# DiplomskiRad.net
KiCad netlist of a schematic drawn in Altium Designer
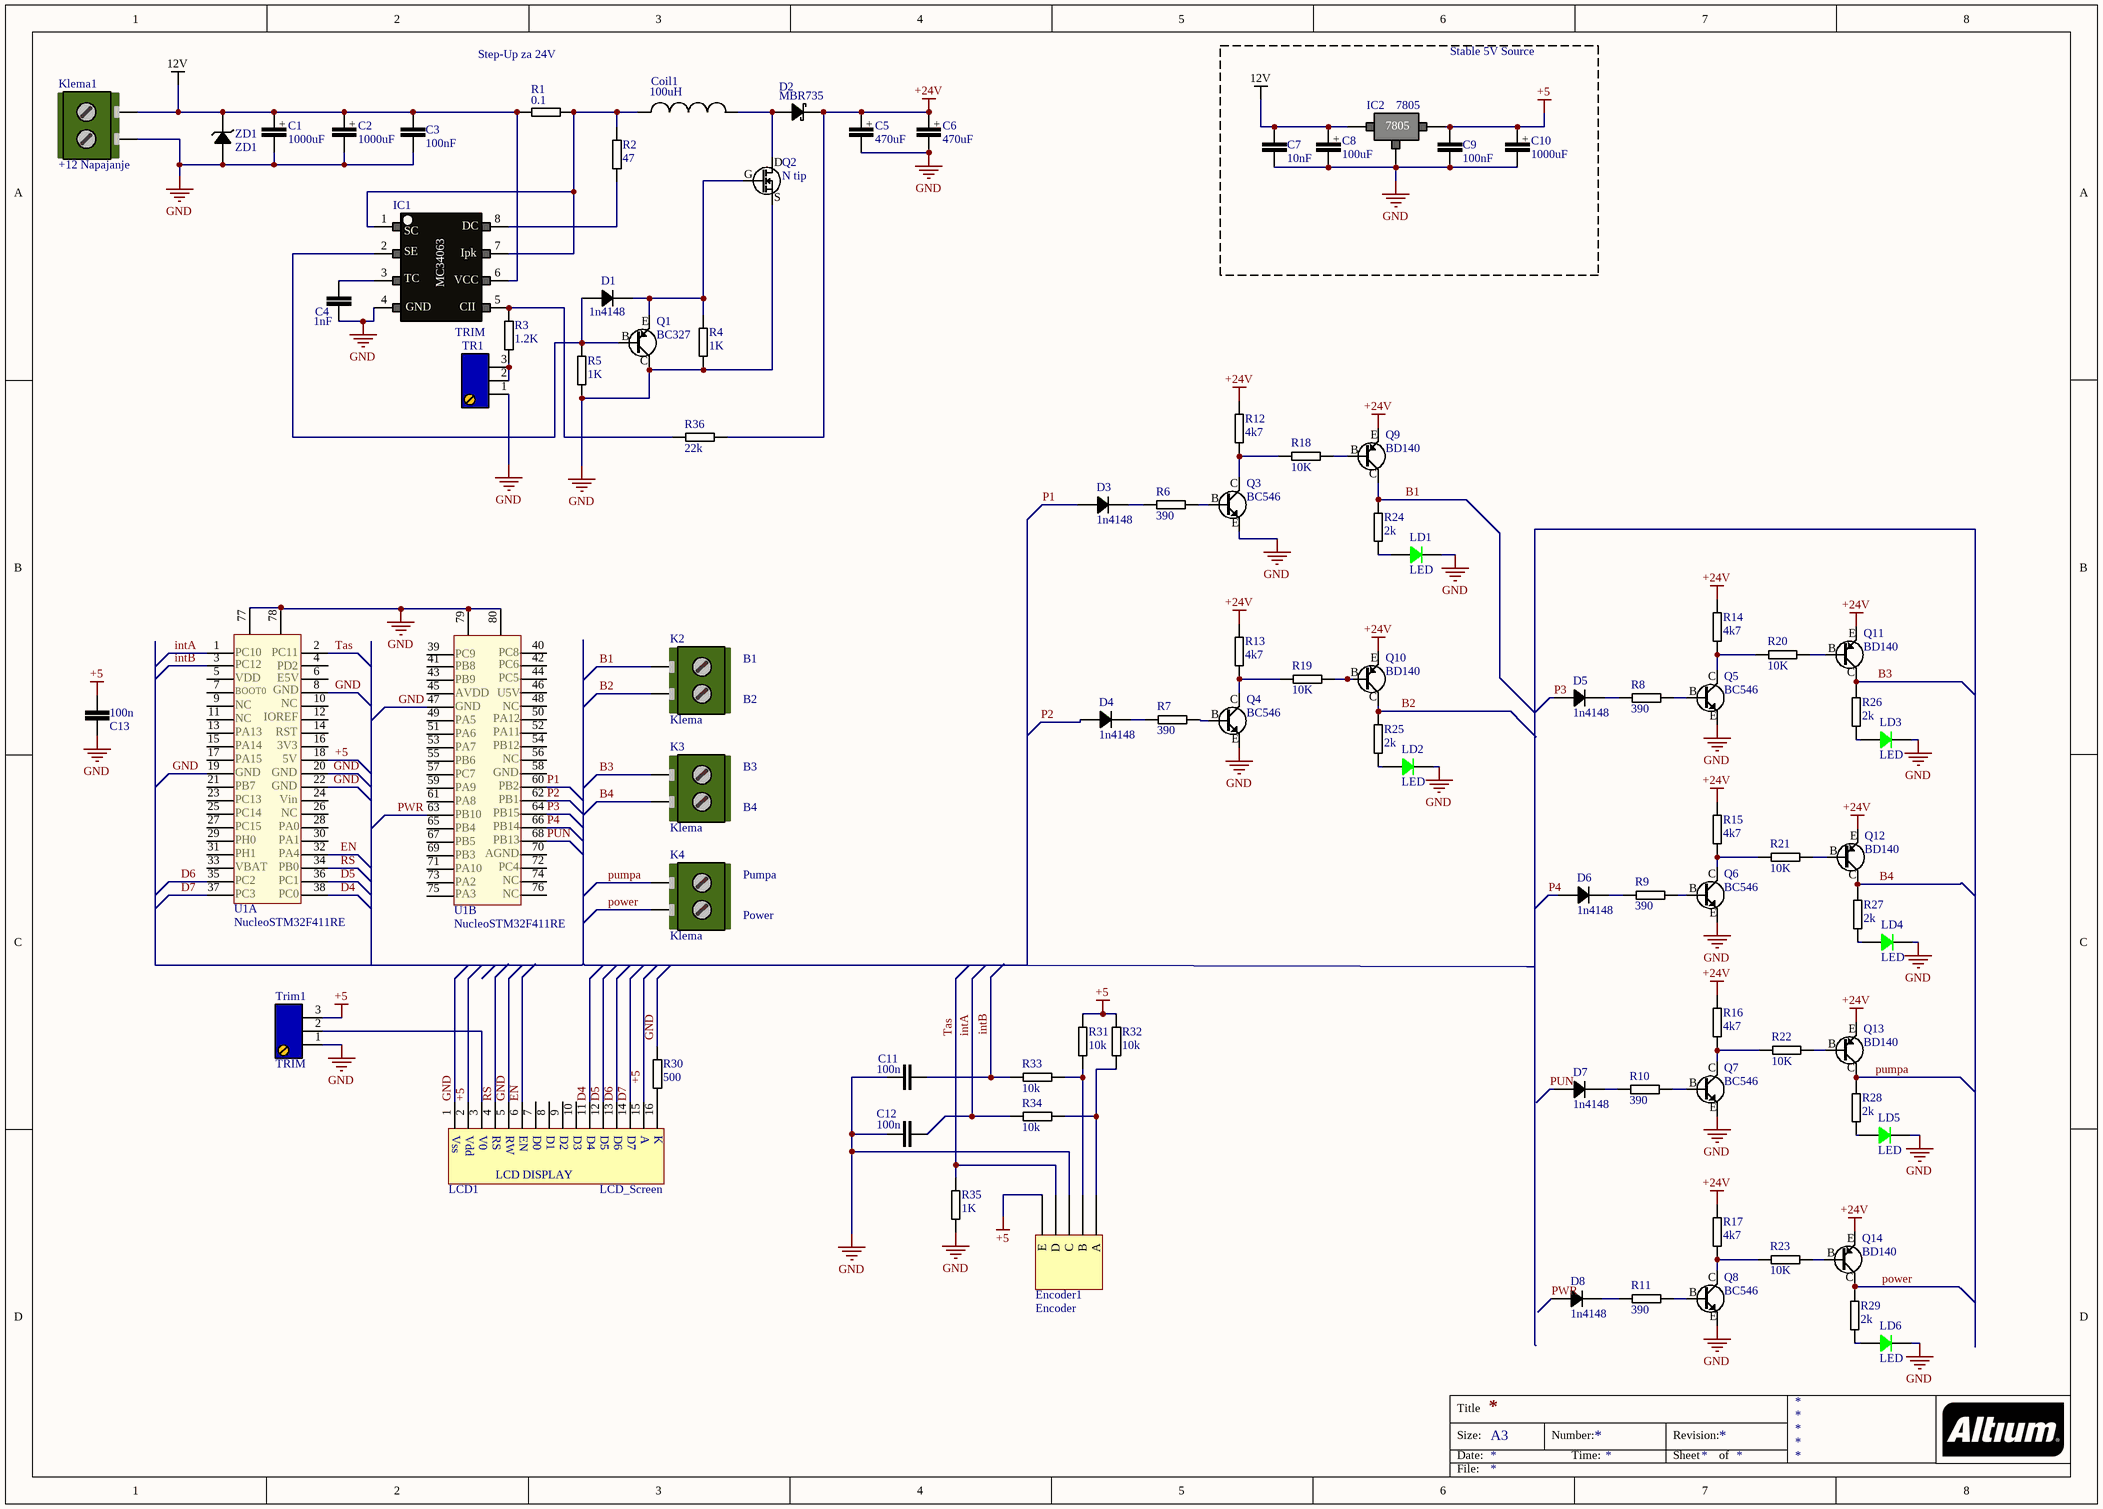
[diagram p0: DiplomskiRad.SchDoc]

(export (version "E")
  (design (tool "Eeschema 10.0.6"))
  (components
    (comp (ref "100n") (value "C13") (footprint "C1(ceramic)") (libsource (lib "KILEX LIB SCH") (part "C1")))
    (comp (ref "C1")
      (value "1000uF")
      (footprint "C2(elektrolit)")
      (libsource (lib "KILEX LIB SCH") (part "C2"))
    )
    (comp (ref "C2")
      (value "1000uF")
      (footprint "C2(elektrolit)")
      (libsource (lib "KILEX LIB SCH") (part "C2"))
    )
    (comp (ref "C3") (value "100nF") (footprint "C1(ceramic)") (libsource (lib "KILEX LIB SCH") (part "C1")))
    (comp (ref "C4") (value "1nF") (footprint "C1(ceramic)") (libsource (lib "KILEX LIB SCH") (part "C1")))
    (comp (ref "C5")
      (value "470uF")
      (footprint "C2(elektrolit)")
      (libsource (lib "KILEX LIB SCH") (part "C2"))
    )
    (comp (ref "C6")
      (value "470uF")
      (footprint "C2(elektrolit)")
      (libsource (lib "KILEX LIB SCH") (part "C2"))
    )
    (comp (ref "C7") (value "10nF") (footprint "C1(ceramic)") (libsource (lib "KILEX LIB SCH") (part "C1")))
    (comp (ref "C8")
      (value "100uF")
      (footprint "C2(elektrolit)")
      (libsource (lib "KILEX LIB SCH") (part "C2"))
    )
    (comp (ref "C9") (value "100nF") (footprint "C1(ceramic)") (libsource (lib "KILEX LIB SCH") (part "C1")))
    (comp (ref "C10")
      (value "1000uF")
      (footprint "C2(elektrolit)")
      (libsource (lib "KILEX LIB SCH") (part "C2"))
    )
    (comp (ref "C11") (value "100n") (footprint "C1(ceramic)") (libsource (lib "KILEX LIB SCH") (part "C1")))
    (comp (ref "C12") (value "100n") (footprint "C1(ceramic)") (libsource (lib "KILEX LIB SCH") (part "C1")))
    (comp (ref "Coil1")
      (value "100uH")
      (footprint "Coil_14x8")
      (libsource (lib "KILEX LIB SCH") (part "Coil"))
    )
    (comp (ref "D1")
      (value "1n4148")
      (footprint "D1(300milsa)")
      (libsource (lib "KILEX LIB SCH") (part "D1"))
    )
    (comp (ref "D2")
      (value "MBR735")
      (footprint "D2(TO220)")
      (libsource (lib "KILEX LIB SCH") (part "Sotki Diode"))
    )
    (comp (ref "D3")
      (value "1n4148")
      (footprint "D1(300milsa)")
      (libsource (lib "KILEX LIB SCH") (part "D1"))
    )
    (comp (ref "D4")
      (value "1n4148")
      (footprint "D1(300milsa)")
      (libsource (lib "KILEX LIB SCH") (part "D1"))
    )
    (comp (ref "D5")
      (value "1n4148")
      (footprint "D1(300milsa)")
      (libsource (lib "KILEX LIB SCH") (part "D1"))
    )
    (comp (ref "D6")
      (value "1n4148")
      (footprint "D1(300milsa)")
      (libsource (lib "KILEX LIB SCH") (part "D1"))
    )
    (comp (ref "D7")
      (value "1n4148")
      (footprint "D1(300milsa)")
      (libsource (lib "KILEX LIB SCH") (part "D1"))
    )
    (comp (ref "D8")
      (value "1n4148")
      (footprint "D1(300milsa)")
      (libsource (lib "KILEX LIB SCH") (part "D1"))
    )
    (comp (ref "Encoder1")
      (value "Encoder")
      (footprint "Encoder")
      (libsource (lib "KILEX LIB SCH") (part "Encoder"))
    )
    (comp (ref "IC1") (value "~") (footprint "DIP8") (libsource (lib "KILEX LIB SCH") (part "MC34063")))
    (comp (ref "IC2") (value "7805") (footprint "TO220") (libsource (lib "KILEX LIB SCH") (part "7805")))
    (comp (ref "K2") (value "Klema") (footprint "Klema") (libsource (lib "") (part "Klema_1")))
    (comp (ref "K3") (value "Klema") (footprint "Klema") (libsource (lib "") (part "Klema_1")))
    (comp (ref "K4") (value "Klema") (footprint "Klema") (libsource (lib "") (part "Klema_1")))
    (comp (ref "Klema1")
      (value "+12 Napajanje")
      (footprint "Klema")
      (libsource (lib "KILEX LIB SCH") (part "Klema"))
    )
    (comp (ref "LCD1")
      (value "LCD_Screen")
      (footprint "LCD_Screen")
      (libsource (lib "KILEX LIB SCH") (part "LCD_Screen"))
    )
    (comp (ref "LD1") (value "LED") (footprint "LED(3mm)") (libsource (lib "KILEX LIB SCH") (part "LED")))
    (comp (ref "LD2") (value "LED") (footprint "LED(3mm)") (libsource (lib "KILEX LIB SCH") (part "LED")))
    (comp (ref "LD3") (value "LED") (footprint "LED(3mm)") (libsource (lib "KILEX LIB SCH") (part "LED")))
    (comp (ref "LD4") (value "LED") (footprint "LED(3mm)") (libsource (lib "KILEX LIB SCH") (part "LED")))
    (comp (ref "LD5") (value "LED") (footprint "LED(3mm)") (libsource (lib "KILEX LIB SCH") (part "LED")))
    (comp (ref "LD6") (value "LED") (footprint "LED(3mm)") (libsource (lib "KILEX LIB SCH") (part "LED")))
    (comp (ref "Q1")
      (value "BC327")
      (footprint "TO-92")
      (libsource (lib "KILEX LIB SCH") (part "Transistor PNP"))
    )
    (comp (ref "Q2")
      (value "N tip")
      (footprint "N-Channel MOSFET")
      (libsource (lib "KILEX LIB SCH") (part "N-Channel MOSFET"))
    )
    (comp (ref "Q3")
      (value "BC546")
      (footprint "TO-92")
      (libsource (lib "KILEX LIB SCH") (part "Transistor NPN"))
    )
    (comp (ref "Q4")
      (value "BC546")
      (footprint "TO-92")
      (libsource (lib "KILEX LIB SCH") (part "Transistor NPN"))
    )
    (comp (ref "Q5")
      (value "BC546")
      (footprint "TO-92")
      (libsource (lib "KILEX LIB SCH") (part "Transistor NPN"))
    )
    (comp (ref "Q6")
      (value "BC546")
      (footprint "TO-92")
      (libsource (lib "KILEX LIB SCH") (part "Transistor NPN"))
    )
    (comp (ref "Q7")
      (value "BC546")
      (footprint "TO-92")
      (libsource (lib "KILEX LIB SCH") (part "Transistor NPN"))
    )
    (comp (ref "Q8")
      (value "BC546")
      (footprint "TO-92")
      (libsource (lib "KILEX LIB SCH") (part "Transistor NPN"))
    )
    (comp (ref "Q9") (value "BD140") (footprint "TO126") (libsource (lib "KILEX LIB SCH") (part "BD140")))
    (comp (ref "Q10") (value "BD140") (footprint "TO126") (libsource (lib "KILEX LIB SCH") (part "BD140")))
    (comp (ref "Q11") (value "BD140") (footprint "TO126") (libsource (lib "KILEX LIB SCH") (part "BD140")))
    (comp (ref "Q12") (value "BD140") (footprint "TO126") (libsource (lib "KILEX LIB SCH") (part "BD140")))
    (comp (ref "Q13") (value "BD140") (footprint "TO126") (libsource (lib "KILEX LIB SCH") (part "BD140")))
    (comp (ref "Q14") (value "BD140") (footprint "TO126") (libsource (lib "KILEX LIB SCH") (part "BD140")))
    (comp (ref "R1") (value "0.1") (footprint "R1(2W)") (libsource (lib "KILEX LIB SCH") (part "R1")))
    (comp (ref "R2") (value "47") (footprint "R1(300milsa)") (libsource (lib "KILEX LIB SCH") (part "R1")))
    (comp (ref "R3") (value "1.2K") (footprint "R1(300milsa)") (libsource (lib "KILEX LIB SCH") (part "R1")))
    (comp (ref "R4") (value "1K") (footprint "R1(300milsa)") (libsource (lib "KILEX LIB SCH") (part "R1")))
    (comp (ref "R5") (value "1K") (footprint "R1(300milsa)") (libsource (lib "KILEX LIB SCH") (part "R1")))
    (comp (ref "R6") (value "390") (footprint "R1(300milsa)") (libsource (lib "KILEX LIB SCH") (part "R1")))
    (comp (ref "R7") (value "390") (footprint "R1(300milsa)") (libsource (lib "KILEX LIB SCH") (part "R1")))
    (comp (ref "R8") (value "390") (footprint "R1(300milsa)") (libsource (lib "KILEX LIB SCH") (part "R1")))
    (comp (ref "R9") (value "390") (footprint "R1(300milsa)") (libsource (lib "KILEX LIB SCH") (part "R1")))
    (comp (ref "R10") (value "390") (footprint "R1(300milsa)") (libsource (lib "KILEX LIB SCH") (part "R1")))
    (comp (ref "R11") (value "390") (footprint "R1(300milsa)") (libsource (lib "KILEX LIB SCH") (part "R1")))
    (comp (ref "R12") (value "4k7") (footprint "R1(300milsa)") (libsource (lib "KILEX LIB SCH") (part "R1")))
    (comp (ref "R13") (value "4k7") (footprint "R1(300milsa)") (libsource (lib "KILEX LIB SCH") (part "R1")))
    (comp (ref "R14") (value "4k7") (footprint "R1(300milsa)") (libsource (lib "KILEX LIB SCH") (part "R1")))
    (comp (ref "R15") (value "4k7") (footprint "R1(300milsa)") (libsource (lib "KILEX LIB SCH") (part "R1")))
    (comp (ref "R16") (value "4k7") (footprint "R1(300milsa)") (libsource (lib "KILEX LIB SCH") (part "R1")))
    (comp (ref "R17") (value "4k7") (footprint "R1(300milsa)") (libsource (lib "KILEX LIB SCH") (part "R1")))
    (comp (ref "R18") (value "10K") (footprint "R1(300milsa)") (libsource (lib "KILEX LIB SCH") (part "R1")))
    (comp (ref "R19") (value "10K") (footprint "R1(300milsa)") (libsource (lib "KILEX LIB SCH") (part "R1")))
    (comp (ref "R20") (value "10K") (footprint "R1(300milsa)") (libsource (lib "KILEX LIB SCH") (part "R1")))
    (comp (ref "R21") (value "10K") (footprint "R1(300milsa)") (libsource (lib "KILEX LIB SCH") (part "R1")))
    (comp (ref "R22") (value "10K") (footprint "R1(300milsa)") (libsource (lib "KILEX LIB SCH") (part "R1")))
    (comp (ref "R23") (value "10K") (footprint "R1(300milsa)") (libsource (lib "KILEX LIB SCH") (part "R1")))
    (comp (ref "R24") (value "2k") (footprint "R1(300milsa)") (libsource (lib "KILEX LIB SCH") (part "R1")))
    (comp (ref "R25") (value "2k") (footprint "R1(300milsa)") (libsource (lib "KILEX LIB SCH") (part "R1")))
    (comp (ref "R26") (value "2k") (footprint "R1(300milsa)") (libsource (lib "KILEX LIB SCH") (part "R1")))
    (comp (ref "R27") (value "2k") (footprint "R1(300milsa)") (libsource (lib "KILEX LIB SCH") (part "R1")))
    (comp (ref "R28") (value "2k") (footprint "R1(300milsa)") (libsource (lib "KILEX LIB SCH") (part "R1")))
    (comp (ref "R29") (value "2k") (footprint "R1(300milsa)") (libsource (lib "KILEX LIB SCH") (part "R1")))
    (comp (ref "R30") (value "500") (footprint "R1(300milsa)") (libsource (lib "KILEX LIB SCH") (part "R1")))
    (comp (ref "R31") (value "10k") (footprint "R1(300milsa)") (libsource (lib "KILEX LIB SCH") (part "R1")))
    (comp (ref "R32") (value "10k") (footprint "R1(300milsa)") (libsource (lib "KILEX LIB SCH") (part "R1")))
    (comp (ref "R33") (value "10k") (footprint "R1(300milsa)") (libsource (lib "KILEX LIB SCH") (part "R1")))
    (comp (ref "R34") (value "10k") (footprint "R1(300milsa)") (libsource (lib "KILEX LIB SCH") (part "R1")))
    (comp (ref "R35") (value "1K") (footprint "R1(300milsa)") (libsource (lib "KILEX LIB SCH") (part "R1")))
    (comp (ref "R36") (value "22k") (footprint "R1(300milsa)") (libsource (lib "KILEX LIB SCH") (part "R1")))
    (comp (ref "TR1") (value "TRIM") (footprint "TRIM") (libsource (lib "KILEX LIB SCH") (part "TRIM")))
    (comp (ref "Trim1") (value "TRIM") (footprint "TRIM") (libsource (lib "KILEX LIB SCH") (part "TRIM")))
    (comp (ref "U1")
      (value "NucleoSTM32F411RE")
      (footprint "Nucleo411")
      (libsource (lib "KILEX LIB SCH") (part "NucleoSTM32F411RE"))
    )
    (comp (ref "ZD1") (value "ZD1") (footprint "D1(300milsa)") (libsource (lib "KILEX LIB SCH") (part "ZD1")))
  )
  (nets
    (net (code "1") (name "+5") (class "Default")
      (node (ref "100n") (pin "2") (pinfunction "2_2") (pintype "passive"))
      (node (ref "C10") (pin "1") (pinfunction "1_1") (pintype "passive"))
      (node (ref "C9") (pin "1") (pinfunction "1_1") (pintype "passive"))
      (node (ref "Encoder1") (pin "5") (pinfunction "E_5") (pintype "passive"))
      (node (ref "IC2") (pin "3") (pinfunction "3_3") (pintype "passive"))
      (node (ref "LCD1") (pin "15") (pinfunction "15_15") (pintype "passive"))
      (node (ref "LCD1") (pin "2") (pinfunction "2_2") (pintype "passive"))
      (node (ref "R31") (pin "2") (pinfunction "2_2") (pintype "passive"))
      (node (ref "R32") (pin "2") (pinfunction "2_2") (pintype "passive"))
      (node (ref "Trim1") (pin "3") (pinfunction "3_3") (pintype "passive"))
      (node (ref "U1") (pin "18") (pinfunction "10_18") (pintype "passive"))
    )
    (net (code "2") (name "+24V") (class "Default")
      (node (ref "C5") (pin "1") (pinfunction "1_1") (pintype "passive"))
      (node (ref "C6") (pin "1") (pinfunction "1_1") (pintype "passive"))
      (node (ref "D2") (pin "2") (pinfunction "2_2") (pintype "passive"))
      (node (ref "Q10") (pin "1") (pinfunction "1_1") (pintype "passive"))
      (node (ref "Q11") (pin "1") (pinfunction "1_1") (pintype "passive"))
      (node (ref "Q12") (pin "1") (pinfunction "1_1") (pintype "passive"))
      (node (ref "Q13") (pin "1") (pinfunction "1_1") (pintype "passive"))
      (node (ref "Q14") (pin "1") (pinfunction "1_1") (pintype "passive"))
      (node (ref "Q9") (pin "1") (pinfunction "1_1") (pintype "passive"))
      (node (ref "R12") (pin "2") (pinfunction "2_2") (pintype "passive"))
      (node (ref "R13") (pin "2") (pinfunction "2_2") (pintype "passive"))
      (node (ref "R14") (pin "2") (pinfunction "2_2") (pintype "passive"))
      (node (ref "R15") (pin "2") (pinfunction "2_2") (pintype "passive"))
      (node (ref "R16") (pin "2") (pinfunction "2_2") (pintype "passive"))
      (node (ref "R17") (pin "2") (pinfunction "2_2") (pintype "passive"))
      (node (ref "R36") (pin "2") (pinfunction "2_2") (pintype "passive"))
    )
    (net (code "3") (name "/B1") (class "Default")
      (node (ref "K2") (pin "1") (pinfunction "1_1") (pintype "passive"))
      (node (ref "Q9") (pin "2") (pinfunction "2_2") (pintype "passive"))
      (node (ref "R24") (pin "1") (pinfunction "1_1") (pintype "passive"))
    )
    (net (code "4") (name "/B2") (class "Default")
      (node (ref "K2") (pin "2") (pinfunction "2_2") (pintype "passive"))
      (node (ref "Q10") (pin "2") (pinfunction "2_2") (pintype "passive"))
      (node (ref "R25") (pin "1") (pinfunction "1_1") (pintype "passive"))
    )
    (net (code "5") (name "/B3") (class "Default")
      (node (ref "K3") (pin "1") (pinfunction "1_1") (pintype "passive"))
      (node (ref "Q11") (pin "2") (pinfunction "2_2") (pintype "passive"))
      (node (ref "R26") (pin "1") (pinfunction "1_1") (pintype "passive"))
    )
    (net (code "6") (name "/B4") (class "Default")
      (node (ref "K3") (pin "2") (pinfunction "2_2") (pintype "passive"))
      (node (ref "Q12") (pin "2") (pinfunction "2_2") (pintype "passive"))
      (node (ref "R27") (pin "1") (pinfunction "1_1") (pintype "passive"))
    )
    (net (code "7") (name "/D4") (class "Default")
      (node (ref "LCD1") (pin "11") (pinfunction "11_11") (pintype "passive"))
      (node (ref "U1") (pin "38") (pinfunction "20_38") (pintype "passive"))
    )
    (net (code "8") (name "/D5") (class "Default")
      (node (ref "LCD1") (pin "12") (pinfunction "12_12") (pintype "passive"))
      (node (ref "U1") (pin "36") (pinfunction "19_36") (pintype "passive"))
    )
    (net (code "9") (name "/D6") (class "Default")
      (node (ref "LCD1") (pin "13") (pinfunction "13_13") (pintype "passive"))
      (node (ref "U1") (pin "35") (pinfunction "18_35") (pintype "passive"))
    )
    (net (code "10") (name "/D7") (class "Default")
      (node (ref "LCD1") (pin "14") (pinfunction "14_14") (pintype "passive"))
      (node (ref "U1") (pin "37") (pinfunction "19_37") (pintype "passive"))
    )
    (net (code "11") (name "/EN") (class "Default")
      (node (ref "LCD1") (pin "6") (pinfunction "6_6") (pintype "passive"))
      (node (ref "U1") (pin "32") (pinfunction "17_32") (pintype "passive"))
    )
    (net (code "12") (name "/P1") (class "Default")
      (node (ref "D3") (pin "1") (pinfunction "1_1") (pintype "passive"))
      (node (ref "U1") (pin "60") (pinfunction "50_60") (pintype "passive"))
    )
    (net (code "13") (name "/P2") (class "Default")
      (node (ref "D4") (pin "1") (pinfunction "1_1") (pintype "passive"))
      (node (ref "U1") (pin "62") (pinfunction "51_62") (pintype "passive"))
    )
    (net (code "14") (name "/P3") (class "Default")
      (node (ref "D5") (pin "1") (pinfunction "1_1") (pintype "passive"))
      (node (ref "U1") (pin "64") (pinfunction "52_64") (pintype "passive"))
    )
    (net (code "15") (name "/P4") (class "Default")
      (node (ref "D6") (pin "1") (pinfunction "1_1") (pintype "passive"))
      (node (ref "U1") (pin "66") (pinfunction "53_66") (pintype "passive"))
    )
    (net (code "16") (name "/PUN") (class "Default")
      (node (ref "D7") (pin "1") (pinfunction "1_1") (pintype "passive"))
      (node (ref "U1") (pin "68") (pinfunction "54_68") (pintype "passive"))
    )
    (net (code "17") (name "/PWR") (class "Default")
      (node (ref "D8") (pin "1") (pinfunction "1_1") (pintype "passive"))
      (node (ref "U1") (pin "63") (pinfunction "51_63") (pintype "passive"))
    )
    (net (code "18") (name "/RS") (class "Default")
      (node (ref "LCD1") (pin "4") (pinfunction "4_4") (pintype "passive"))
      (node (ref "U1") (pin "34") (pinfunction "18_34") (pintype "passive"))
    )
    (net (code "19") (name "/Tas") (class "Default")
      (node (ref "Encoder1") (pin "4") (pinfunction "D_4") (pintype "passive"))
      (node (ref "R35") (pin "1") (pinfunction "1_1") (pintype "passive"))
      (node (ref "U1") (pin "2") (pinfunction "2_2") (pintype "passive"))
    )
    (net (code "20") (name "/intA") (class "Default")
      (node (ref "C12") (pin "1") (pinfunction "1_1") (pintype "passive"))
      (node (ref "R34") (pin "2") (pinfunction "2_2") (pintype "passive"))
      (node (ref "U1") (pin "1") (pinfunction "1_1") (pintype "passive"))
    )
    (net (code "21") (name "/intB") (class "Default")
      (node (ref "C11") (pin "2") (pinfunction "2_2") (pintype "passive"))
      (node (ref "R33") (pin "2") (pinfunction "2_2") (pintype "passive"))
      (node (ref "U1") (pin "3") (pinfunction "2_3") (pintype "passive"))
    )
    (net (code "22") (name "/power") (class "Default")
      (node (ref "K4") (pin "2") (pinfunction "2_2") (pintype "passive"))
      (node (ref "Q14") (pin "2") (pinfunction "2_2") (pintype "passive"))
      (node (ref "R29") (pin "1") (pinfunction "1_1") (pintype "passive"))
    )
    (net (code "23") (name "/pumpa") (class "Default")
      (node (ref "K4") (pin "1") (pinfunction "1_1") (pintype "passive"))
      (node (ref "Q13") (pin "2") (pinfunction "2_2") (pintype "passive"))
      (node (ref "R28") (pin "1") (pinfunction "1_1") (pintype "passive"))
    )
    (net (code "24") (name "12V") (class "Default")
      (node (ref "C1") (pin "1") (pinfunction "1_1") (pintype "passive"))
      (node (ref "C2") (pin "1") (pinfunction "1_1") (pintype "passive"))
      (node (ref "C3") (pin "2") (pinfunction "2_2") (pintype "passive"))
      (node (ref "C7") (pin "1") (pinfunction "1_1") (pintype "passive"))
      (node (ref "C8") (pin "1") (pinfunction "1_1") (pintype "passive"))
      (node (ref "IC1") (pin "6") (pinfunction "6_6") (pintype "passive"))
      (node (ref "IC2") (pin "1") (pinfunction "1_1") (pintype "passive"))
      (node (ref "Klema1") (pin "2") (pinfunction "2_2") (pintype "passive"))
      (node (ref "R1") (pin "1") (pinfunction "1_1") (pintype "passive"))
      (node (ref "ZD1") (pin "2") (pinfunction "2_2") (pintype "passive"))
    )
    (net (code "25") (name "GND") (class "Default")
      (node (ref "100n") (pin "1") (pinfunction "1_1") (pintype "passive"))
      (node (ref "C1") (pin "2") (pinfunction "2_2") (pintype "passive"))
      (node (ref "C10") (pin "2") (pinfunction "2_2") (pintype "passive"))
      (node (ref "C11") (pin "1") (pinfunction "1_1") (pintype "passive"))
      (node (ref "C12") (pin "2") (pinfunction "2_2") (pintype "passive"))
      (node (ref "C2") (pin "2") (pinfunction "2_2") (pintype "passive"))
      (node (ref "C3") (pin "1") (pinfunction "1_1") (pintype "passive"))
      (node (ref "C4") (pin "1") (pinfunction "1_1") (pintype "passive"))
      (node (ref "C5") (pin "2") (pinfunction "2_2") (pintype "passive"))
      (node (ref "C6") (pin "2") (pinfunction "2_2") (pintype "passive"))
      (node (ref "C7") (pin "2") (pinfunction "2_2") (pintype "passive"))
      (node (ref "C8") (pin "2") (pinfunction "2_2") (pintype "passive"))
      (node (ref "C9") (pin "2") (pinfunction "2_2") (pintype "passive"))
      (node (ref "Encoder1") (pin "3") (pinfunction "C_3") (pintype "passive"))
      (node (ref "IC1") (pin "4") (pinfunction "4_4") (pintype "passive"))
      (node (ref "IC2") (pin "2") (pinfunction "2_2") (pintype "passive"))
      (node (ref "Klema1") (pin "1") (pinfunction "1_1") (pintype "passive"))
      (node (ref "LCD1") (pin "1") (pinfunction "1_1") (pintype "passive"))
      (node (ref "LCD1") (pin "5") (pinfunction "5_5") (pintype "passive"))
      (node (ref "LD1") (pin "2") (pinfunction "2_2") (pintype "passive"))
      (node (ref "LD2") (pin "2") (pinfunction "2_2") (pintype "passive"))
      (node (ref "LD3") (pin "2") (pinfunction "2_2") (pintype "passive"))
      (node (ref "LD4") (pin "2") (pinfunction "2_2") (pintype "passive"))
      (node (ref "LD5") (pin "2") (pinfunction "2_2") (pintype "passive"))
      (node (ref "LD6") (pin "2") (pinfunction "2_2") (pintype "passive"))
      (node (ref "Q1") (pin "3") (pinfunction "3_3") (pintype "passive"))
      (node (ref "Q2") (pin "3") (pinfunction "3_3") (pintype "passive"))
      (node (ref "Q3") (pin "2") (pinfunction "2_2") (pintype "passive"))
      (node (ref "Q4") (pin "2") (pinfunction "2_2") (pintype "passive"))
      (node (ref "Q5") (pin "2") (pinfunction "2_2") (pintype "passive"))
      (node (ref "Q6") (pin "2") (pinfunction "2_2") (pintype "passive"))
      (node (ref "Q7") (pin "2") (pinfunction "2_2") (pintype "passive"))
      (node (ref "Q8") (pin "2") (pinfunction "2_2") (pintype "passive"))
      (node (ref "R30") (pin "2") (pinfunction "2_2") (pintype "passive"))
      (node (ref "R35") (pin "2") (pinfunction "2_2") (pintype "passive"))
      (node (ref "R4") (pin "1") (pinfunction "1_1") (pintype "passive"))
      (node (ref "R5") (pin "1") (pinfunction "1_1") (pintype "passive"))
      (node (ref "TR1") (pin "1") (pinfunction "1_1") (pintype "passive"))
      (node (ref "Trim1") (pin "1") (pinfunction "1_1") (pintype "passive"))
      (node (ref "U1") (pin "19") (pinfunction "10_19") (pintype "passive"))
      (node (ref "U1") (pin "20") (pinfunction "11_20") (pintype "passive"))
      (node (ref "U1") (pin "22") (pinfunction "12_22") (pintype "passive"))
      (node (ref "U1") (pin "47") (pinfunction "43_47") (pintype "passive"))
      (node (ref "U1") (pin "77") (pinfunction "77_77") (pintype "passive"))
      (node (ref "U1") (pin "78") (pinfunction "78_78") (pintype "passive"))
      (node (ref "U1") (pin "79") (pinfunction "79_79") (pintype "passive"))
      (node (ref "U1") (pin "8") (pinfunction "5_8") (pintype "passive"))
      (node (ref "U1") (pin "80") (pinfunction "80_80") (pintype "passive"))
      (node (ref "ZD1") (pin "1") (pinfunction "1_1") (pintype "passive"))
    )
    (net (code "26") (name "Net-(C4-Pad2)") (class "Default")
      (node (ref "C4") (pin "2") (pinfunction "2_2") (pintype "passive"))
      (node (ref "IC1") (pin "3") (pinfunction "3_3") (pintype "passive"))
    )
    (net (code "27") (name "Net-(Coil1-Pad1)") (class "Default")
      (node (ref "Coil1") (pin "1") (pinfunction "1_1") (pintype "passive"))
      (node (ref "IC1") (pin "1") (pinfunction "1_1") (pintype "passive"))
      (node (ref "IC1") (pin "7") (pinfunction "7_7") (pintype "passive"))
      (node (ref "R1") (pin "2") (pinfunction "2_2") (pintype "passive"))
      (node (ref "R2") (pin "2") (pinfunction "2_2") (pintype "passive"))
    )
    (net (code "28") (name "Net-(Coil1-Pad2)") (class "Default")
      (node (ref "Coil1") (pin "2") (pintype "passive"))
      (node (ref "D2") (pin "1") (pinfunction "1_1") (pintype "passive"))
      (node (ref "Q2") (pin "2") (pinfunction "2_2") (pintype "passive"))
    )
    (net (code "29") (name "Net-(D1-Pad1)") (class "Default")
      (node (ref "D1") (pin "1") (pinfunction "1_1") (pintype "passive"))
      (node (ref "IC1") (pin "2") (pinfunction "2_2") (pintype "passive"))
      (node (ref "Q1") (pin "1") (pinfunction "1_1") (pintype "passive"))
      (node (ref "R5") (pin "2") (pinfunction "2_2") (pintype "passive"))
    )
    (net (code "30") (name "Net-(D1-Pad2)") (class "Default")
      (node (ref "D1") (pin "2") (pinfunction "2_2") (pintype "passive"))
      (node (ref "Q1") (pin "2") (pinfunction "2_2") (pintype "passive"))
      (node (ref "Q2") (pin "1") (pinfunction "1_1") (pintype "passive"))
      (node (ref "R4") (pin "2") (pinfunction "2_2") (pintype "passive"))
    )
    (net (code "31") (name "Net-(D3-Pad2)") (class "Default")
      (node (ref "D3") (pin "2") (pinfunction "2_2") (pintype "passive"))
      (node (ref "R6") (pin "1") (pinfunction "1_1") (pintype "passive"))
    )
    (net (code "32") (name "Net-(D4-Pad2)") (class "Default")
      (node (ref "D4") (pin "2") (pinfunction "2_2") (pintype "passive"))
      (node (ref "R7") (pin "1") (pinfunction "1_1") (pintype "passive"))
    )
    (net (code "33") (name "Net-(D5-Pad2)") (class "Default")
      (node (ref "D5") (pin "2") (pinfunction "2_2") (pintype "passive"))
      (node (ref "R8") (pin "1") (pinfunction "1_1") (pintype "passive"))
    )
    (net (code "34") (name "Net-(D6-Pad2)") (class "Default")
      (node (ref "D6") (pin "2") (pinfunction "2_2") (pintype "passive"))
      (node (ref "R9") (pin "1") (pinfunction "1_1") (pintype "passive"))
    )
    (net (code "35") (name "Net-(D7-Pad2)") (class "Default")
      (node (ref "D7") (pin "2") (pinfunction "2_2") (pintype "passive"))
      (node (ref "R10") (pin "1") (pinfunction "1_1") (pintype "passive"))
    )
    (net (code "36") (name "Net-(D8-Pad2)") (class "Default")
      (node (ref "D8") (pin "2") (pinfunction "2_2") (pintype "passive"))
      (node (ref "R11") (pin "1") (pinfunction "1_1") (pintype "passive"))
    )
    (net (code "37") (name "Net-(Encoder1-A)") (class "Default")
      (node (ref "Encoder1") (pin "1") (pinfunction "A_1") (pintype "passive"))
      (node (ref "R32") (pin "1") (pinfunction "1_1") (pintype "passive"))
      (node (ref "R34") (pin "1") (pinfunction "1_1") (pintype "passive"))
    )
    (net (code "38") (name "Net-(Encoder1-B)") (class "Default")
      (node (ref "Encoder1") (pin "2") (pinfunction "B_2") (pintype "passive"))
      (node (ref "R31") (pin "1") (pinfunction "1_1") (pintype "passive"))
      (node (ref "R33") (pin "1") (pinfunction "1_1") (pintype "passive"))
    )
    (net (code "39") (name "Net-(IC1-Pad5)") (class "Default")
      (node (ref "IC1") (pin "5") (pinfunction "5_5") (pintype "passive"))
      (node (ref "R3") (pin "2") (pinfunction "2_2") (pintype "passive"))
      (node (ref "R36") (pin "1") (pinfunction "1_1") (pintype "passive"))
    )
    (net (code "40") (name "Net-(IC1-Pad8)") (class "Default")
      (node (ref "IC1") (pin "8") (pinfunction "8_8") (pintype "passive"))
      (node (ref "R2") (pin "1") (pinfunction "1_1") (pintype "passive"))
    )
    (net (code "41") (name "Net-(LCD1-Pad3)") (class "Default")
      (node (ref "LCD1") (pin "3") (pinfunction "3_3") (pintype "passive"))
      (node (ref "Trim1") (pin "2") (pinfunction "2_2") (pintype "passive"))
    )
    (net (code "42") (name "Net-(LCD1-Pad16)") (class "Default")
      (node (ref "LCD1") (pin "16") (pinfunction "16_16") (pintype "passive"))
      (node (ref "R30") (pin "1") (pinfunction "1_1") (pintype "passive"))
    )
    (net (code "43") (name "Net-(LD1-Pad1)") (class "Default")
      (node (ref "LD1") (pin "1") (pinfunction "1_1") (pintype "passive"))
      (node (ref "R24") (pin "2") (pinfunction "2_2") (pintype "passive"))
    )
    (net (code "44") (name "Net-(LD2-Pad1)") (class "Default")
      (node (ref "LD2") (pin "1") (pinfunction "1_1") (pintype "passive"))
      (node (ref "R25") (pin "2") (pinfunction "2_2") (pintype "passive"))
    )
    (net (code "45") (name "Net-(LD3-Pad1)") (class "Default")
      (node (ref "LD3") (pin "1") (pinfunction "1_1") (pintype "passive"))
      (node (ref "R26") (pin "2") (pinfunction "2_2") (pintype "passive"))
    )
    (net (code "46") (name "Net-(LD4-Pad1)") (class "Default")
      (node (ref "LD4") (pin "1") (pinfunction "1_1") (pintype "passive"))
      (node (ref "R27") (pin "2") (pinfunction "2_2") (pintype "passive"))
    )
    (net (code "47") (name "Net-(LD5-Pad1)") (class "Default")
      (node (ref "LD5") (pin "1") (pinfunction "1_1") (pintype "passive"))
      (node (ref "R28") (pin "2") (pinfunction "2_2") (pintype "passive"))
    )
    (net (code "48") (name "Net-(LD6-Pad1)") (class "Default")
      (node (ref "LD6") (pin "1") (pinfunction "1_1") (pintype "passive"))
      (node (ref "R29") (pin "2") (pinfunction "2_2") (pintype "passive"))
    )
    (net (code "49") (name "Net-(Q3-Pad1)") (class "Default")
      (node (ref "Q3") (pin "1") (pinfunction "1_1") (pintype "passive"))
      (node (ref "R6") (pin "2") (pinfunction "2_2") (pintype "passive"))
    )
    (net (code "50") (name "Net-(Q3-Pad3)") (class "Default")
      (node (ref "Q3") (pin "3") (pinfunction "3_3") (pintype "passive"))
      (node (ref "R12") (pin "1") (pinfunction "1_1") (pintype "passive"))
      (node (ref "R18") (pin "1") (pinfunction "1_1") (pintype "passive"))
    )
    (net (code "51") (name "Net-(Q4-Pad1)") (class "Default")
      (node (ref "Q4") (pin "1") (pinfunction "1_1") (pintype "passive"))
      (node (ref "R7") (pin "2") (pinfunction "2_2") (pintype "passive"))
    )
    (net (code "52") (name "Net-(Q4-Pad3)") (class "Default")
      (node (ref "Q4") (pin "3") (pinfunction "3_3") (pintype "passive"))
      (node (ref "R13") (pin "1") (pinfunction "1_1") (pintype "passive"))
      (node (ref "R19") (pin "1") (pinfunction "1_1") (pintype "passive"))
    )
    (net (code "53") (name "Net-(Q5-Pad1)") (class "Default")
      (node (ref "Q5") (pin "1") (pinfunction "1_1") (pintype "passive"))
      (node (ref "R8") (pin "2") (pinfunction "2_2") (pintype "passive"))
    )
    (net (code "54") (name "Net-(Q5-Pad3)") (class "Default")
      (node (ref "Q5") (pin "3") (pinfunction "3_3") (pintype "passive"))
      (node (ref "R14") (pin "1") (pinfunction "1_1") (pintype "passive"))
      (node (ref "R20") (pin "1") (pinfunction "1_1") (pintype "passive"))
    )
    (net (code "55") (name "Net-(Q6-Pad1)") (class "Default")
      (node (ref "Q6") (pin "1") (pinfunction "1_1") (pintype "passive"))
      (node (ref "R9") (pin "2") (pinfunction "2_2") (pintype "passive"))
    )
    (net (code "56") (name "Net-(Q6-Pad3)") (class "Default")
      (node (ref "Q6") (pin "3") (pinfunction "3_3") (pintype "passive"))
      (node (ref "R15") (pin "1") (pinfunction "1_1") (pintype "passive"))
      (node (ref "R21") (pin "1") (pinfunction "1_1") (pintype "passive"))
    )
    (net (code "57") (name "Net-(Q7-Pad1)") (class "Default")
      (node (ref "Q7") (pin "1") (pinfunction "1_1") (pintype "passive"))
      (node (ref "R10") (pin "2") (pinfunction "2_2") (pintype "passive"))
    )
    (net (code "58") (name "Net-(Q7-Pad3)") (class "Default")
      (node (ref "Q7") (pin "3") (pinfunction "3_3") (pintype "passive"))
      (node (ref "R16") (pin "1") (pinfunction "1_1") (pintype "passive"))
      (node (ref "R22") (pin "1") (pinfunction "1_1") (pintype "passive"))
    )
    (net (code "59") (name "Net-(Q8-Pad1)") (class "Default")
      (node (ref "Q8") (pin "1") (pinfunction "1_1") (pintype "passive"))
      (node (ref "R11") (pin "2") (pinfunction "2_2") (pintype "passive"))
    )
    (net (code "60") (name "Net-(Q8-Pad3)") (class "Default")
      (node (ref "Q8") (pin "3") (pinfunction "3_3") (pintype "passive"))
      (node (ref "R17") (pin "1") (pinfunction "1_1") (pintype "passive"))
      (node (ref "R23") (pin "1") (pinfunction "1_1") (pintype "passive"))
    )
    (net (code "61") (name "Net-(Q9-Pad3)") (class "Default")
      (node (ref "Q9") (pin "3") (pinfunction "3_3") (pintype "passive"))
      (node (ref "R18") (pin "2") (pinfunction "2_2") (pintype "passive"))
    )
    (net (code "62") (name "Net-(Q10-Pad3)") (class "Default")
      (node (ref "Q10") (pin "3") (pinfunction "3_3") (pintype "passive"))
      (node (ref "R19") (pin "2") (pinfunction "2_2") (pintype "passive"))
    )
    (net (code "63") (name "Net-(Q11-Pad3)") (class "Default")
      (node (ref "Q11") (pin "3") (pinfunction "3_3") (pintype "passive"))
      (node (ref "R20") (pin "2") (pinfunction "2_2") (pintype "passive"))
    )
    (net (code "64") (name "Net-(Q12-Pad3)") (class "Default")
      (node (ref "Q12") (pin "3") (pinfunction "3_3") (pintype "passive"))
      (node (ref "R21") (pin "2") (pinfunction "2_2") (pintype "passive"))
    )
    (net (code "65") (name "Net-(Q13-Pad3)") (class "Default")
      (node (ref "Q13") (pin "3") (pinfunction "3_3") (pintype "passive"))
      (node (ref "R22") (pin "2") (pinfunction "2_2") (pintype "passive"))
    )
    (net (code "66") (name "Net-(Q14-Pad3)") (class "Default")
      (node (ref "Q14") (pin "3") (pinfunction "3_3") (pintype "passive"))
      (node (ref "R23") (pin "2") (pinfunction "2_2") (pintype "passive"))
    )
    (net (code "67") (name "Net-(R3-Pad1)") (class "Default")
      (node (ref "R3") (pin "1") (pinfunction "1_1") (pintype "passive"))
      (node (ref "TR1") (pin "2") (pinfunction "2_2") (pintype "passive"))
      (node (ref "TR1") (pin "3") (pinfunction "3_3") (pintype "passive"))
    )
    (net (code "68") (name "unconnected-(LCD1-Pad7)") (class "Default")
      (node (ref "LCD1") (pin "7") (pinfunction "7_7") (pintype "passive"))
    )
    (net (code "69") (name "unconnected-(LCD1-Pad8)") (class "Default")
      (node (ref "LCD1") (pin "8") (pinfunction "8_8") (pintype "passive"))
    )
    (net (code "70") (name "unconnected-(LCD1-Pad9)") (class "Default")
      (node (ref "LCD1") (pin "9") (pinfunction "9_9") (pintype "passive"))
    )
    (net (code "71") (name "unconnected-(LCD1-Pad10)") (class "Default")
      (node (ref "LCD1") (pin "10") (pinfunction "10_10") (pintype "passive"))
    )
    (net (code "72") (name "unconnected-(U1-Pad39)") (class "Default")
      (node (ref "U1") (pin "39") (pinfunction "39_39") (pintype "passive"))
    )
    (net (code "73") (name "unconnected-(U1-Pad40)") (class "Default")
      (node (ref "U1") (pin "40") (pinfunction "40_40") (pintype "passive"))
    )
    (net (code "74") (name "unconnected-(U1A-3-Pad4)") (class "Default")
      (node (ref "U1") (pin "4") (pinfunction "3_4") (pintype "passive"))
    )
    (net (code "75") (name "unconnected-(U1A-3-Pad5)") (class "Default")
      (node (ref "U1") (pin "5") (pinfunction "3_5") (pintype "passive"))
    )
    (net (code "76") (name "unconnected-(U1A-4-Pad6)") (class "Default")
      (node (ref "U1") (pin "6") (pinfunction "4_6") (pintype "passive"))
    )
    (net (code "77") (name "unconnected-(U1A-4-Pad7)") (class "Default")
      (node (ref "U1") (pin "7") (pinfunction "4_7") (pintype "passive"))
    )
    (net (code "78") (name "unconnected-(U1A-5-Pad9)") (class "Default")
      (node (ref "U1") (pin "9") (pinfunction "5_9") (pintype "passive"))
    )
    (net (code "79") (name "unconnected-(U1A-6-Pad10)") (class "Default")
      (node (ref "U1") (pin "10") (pinfunction "6_10") (pintype "passive"))
    )
    (net (code "80") (name "unconnected-(U1A-6-Pad11)") (class "Default")
      (node (ref "U1") (pin "11") (pinfunction "6_11") (pintype "passive"))
    )
    (net (code "81") (name "unconnected-(U1A-7-Pad12)") (class "Default")
      (node (ref "U1") (pin "12") (pinfunction "7_12") (pintype "passive"))
    )
    (net (code "82") (name "unconnected-(U1A-7-Pad13)") (class "Default")
      (node (ref "U1") (pin "13") (pinfunction "7_13") (pintype "passive"))
    )
    (net (code "83") (name "unconnected-(U1A-8-Pad14)") (class "Default")
      (node (ref "U1") (pin "14") (pinfunction "8_14") (pintype "passive"))
    )
    (net (code "84") (name "unconnected-(U1A-8-Pad15)") (class "Default")
      (node (ref "U1") (pin "15") (pinfunction "8_15") (pintype "passive"))
    )
    (net (code "85") (name "unconnected-(U1A-9-Pad16)") (class "Default")
      (node (ref "U1") (pin "16") (pinfunction "9_16") (pintype "passive"))
    )
    (net (code "86") (name "unconnected-(U1A-9-Pad17)") (class "Default")
      (node (ref "U1") (pin "17") (pinfunction "9_17") (pintype "passive"))
    )
    (net (code "87") (name "unconnected-(U1A-11-Pad21)") (class "Default")
      (node (ref "U1") (pin "21") (pinfunction "11_21") (pintype "passive"))
    )
    (net (code "88") (name "unconnected-(U1A-12-Pad23)") (class "Default")
      (node (ref "U1") (pin "23") (pinfunction "12_23") (pintype "passive"))
    )
    (net (code "89") (name "unconnected-(U1A-13-Pad24)") (class "Default")
      (node (ref "U1") (pin "24") (pinfunction "13_24") (pintype "passive"))
    )
    (net (code "90") (name "unconnected-(U1A-13-Pad25)") (class "Default")
      (node (ref "U1") (pin "25") (pinfunction "13_25") (pintype "passive"))
    )
    (net (code "91") (name "unconnected-(U1A-14-Pad26)") (class "Default")
      (node (ref "U1") (pin "26") (pinfunction "14_26") (pintype "passive"))
    )
    (net (code "92") (name "unconnected-(U1A-14-Pad27)") (class "Default")
      (node (ref "U1") (pin "27") (pinfunction "14_27") (pintype "passive"))
    )
    (net (code "93") (name "unconnected-(U1A-15-Pad28)") (class "Default")
      (node (ref "U1") (pin "28") (pinfunction "15_28") (pintype "passive"))
    )
    (net (code "94") (name "unconnected-(U1A-15-Pad29)") (class "Default")
      (node (ref "U1") (pin "29") (pinfunction "15_29") (pintype "passive"))
    )
    (net (code "95") (name "unconnected-(U1A-16-Pad30)") (class "Default")
      (node (ref "U1") (pin "30") (pinfunction "16_30") (pintype "passive"))
    )
    (net (code "96") (name "unconnected-(U1A-16-Pad31)") (class "Default")
      (node (ref "U1") (pin "31") (pinfunction "16_31") (pintype "passive"))
    )
    (net (code "97") (name "unconnected-(U1A-17-Pad33)") (class "Default")
      (node (ref "U1") (pin "33") (pinfunction "17_33") (pintype "passive"))
    )
    (net (code "98") (name "unconnected-(U1B-40-Pad41)") (class "Default")
      (node (ref "U1") (pin "41") (pinfunction "40_41") (pintype "passive"))
    )
    (net (code "99") (name "unconnected-(U1B-41-Pad42)") (class "Default")
      (node (ref "U1") (pin "42") (pinfunction "41_42") (pintype "passive"))
    )
    (net (code "100") (name "unconnected-(U1B-41-Pad43)") (class "Default")
      (node (ref "U1") (pin "43") (pinfunction "41_43") (pintype "passive"))
    )
    (net (code "101") (name "unconnected-(U1B-42-Pad44)") (class "Default")
      (node (ref "U1") (pin "44") (pinfunction "42_44") (pintype "passive"))
    )
    (net (code "102") (name "unconnected-(U1B-42-Pad45)") (class "Default")
      (node (ref "U1") (pin "45") (pinfunction "42_45") (pintype "passive"))
    )
    (net (code "103") (name "unconnected-(U1B-43-Pad46)") (class "Default")
      (node (ref "U1") (pin "46") (pinfunction "43_46") (pintype "passive"))
    )
    (net (code "104") (name "unconnected-(U1B-44-Pad48)") (class "Default")
      (node (ref "U1") (pin "48") (pinfunction "44_48") (pintype "passive"))
    )
    (net (code "105") (name "unconnected-(U1B-44-Pad49)") (class "Default")
      (node (ref "U1") (pin "49") (pinfunction "44_49") (pintype "passive"))
    )
    (net (code "106") (name "unconnected-(U1B-45-Pad50)") (class "Default")
      (node (ref "U1") (pin "50") (pinfunction "45_50") (pintype "passive"))
    )
    (net (code "107") (name "unconnected-(U1B-45-Pad51)") (class "Default")
      (node (ref "U1") (pin "51") (pinfunction "45_51") (pintype "passive"))
    )
    (net (code "108") (name "unconnected-(U1B-46-Pad52)") (class "Default")
      (node (ref "U1") (pin "52") (pinfunction "46_52") (pintype "passive"))
    )
    (net (code "109") (name "unconnected-(U1B-46-Pad53)") (class "Default")
      (node (ref "U1") (pin "53") (pinfunction "46_53") (pintype "passive"))
    )
    (net (code "110") (name "unconnected-(U1B-47-Pad54)") (class "Default")
      (node (ref "U1") (pin "54") (pinfunction "47_54") (pintype "passive"))
    )
    (net (code "111") (name "unconnected-(U1B-47-Pad55)") (class "Default")
      (node (ref "U1") (pin "55") (pinfunction "47_55") (pintype "passive"))
    )
    (net (code "112") (name "unconnected-(U1B-48-Pad56)") (class "Default")
      (node (ref "U1") (pin "56") (pinfunction "48_56") (pintype "passive"))
    )
    (net (code "113") (name "unconnected-(U1B-48-Pad57)") (class "Default")
      (node (ref "U1") (pin "57") (pinfunction "48_57") (pintype "passive"))
    )
    (net (code "114") (name "unconnected-(U1B-49-Pad58)") (class "Default")
      (node (ref "U1") (pin "58") (pinfunction "49_58") (pintype "passive"))
    )
    (net (code "115") (name "unconnected-(U1B-49-Pad59)") (class "Default")
      (node (ref "U1") (pin "59") (pinfunction "49_59") (pintype "passive"))
    )
    (net (code "116") (name "unconnected-(U1B-50-Pad61)") (class "Default")
      (node (ref "U1") (pin "61") (pinfunction "50_61") (pintype "passive"))
    )
    (net (code "117") (name "unconnected-(U1B-52-Pad65)") (class "Default")
      (node (ref "U1") (pin "65") (pinfunction "52_65") (pintype "passive"))
    )
    (net (code "118") (name "unconnected-(U1B-53-Pad67)") (class "Default")
      (node (ref "U1") (pin "67") (pinfunction "53_67") (pintype "passive"))
    )
    (net (code "119") (name "unconnected-(U1B-54-Pad69)") (class "Default")
      (node (ref "U1") (pin "69") (pinfunction "54_69") (pintype "passive"))
    )
    (net (code "120") (name "unconnected-(U1B-55-Pad70)") (class "Default")
      (node (ref "U1") (pin "70") (pinfunction "55_70") (pintype "passive"))
    )
    (net (code "121") (name "unconnected-(U1B-55-Pad71)") (class "Default")
      (node (ref "U1") (pin "71") (pinfunction "55_71") (pintype "passive"))
    )
    (net (code "122") (name "unconnected-(U1B-56-Pad72)") (class "Default")
      (node (ref "U1") (pin "72") (pinfunction "56_72") (pintype "passive"))
    )
    (net (code "123") (name "unconnected-(U1B-56-Pad73)") (class "Default")
      (node (ref "U1") (pin "73") (pinfunction "56_73") (pintype "passive"))
    )
    (net (code "124") (name "unconnected-(U1B-57-Pad74)") (class "Default")
      (node (ref "U1") (pin "74") (pinfunction "57_74") (pintype "passive"))
    )
    (net (code "125") (name "unconnected-(U1B-57-Pad75)") (class "Default")
      (node (ref "U1") (pin "75") (pinfunction "57_75") (pintype "passive"))
    )
    (net (code "126") (name "unconnected-(U1B-58-Pad76)") (class "Default")
      (node (ref "U1") (pin "76") (pinfunction "58_76") (pintype "passive"))
    )
  )
)
